# Brushless_2015RevA1_OptEnc.net
KiCad netlist of a schematic drawn in EAGLE
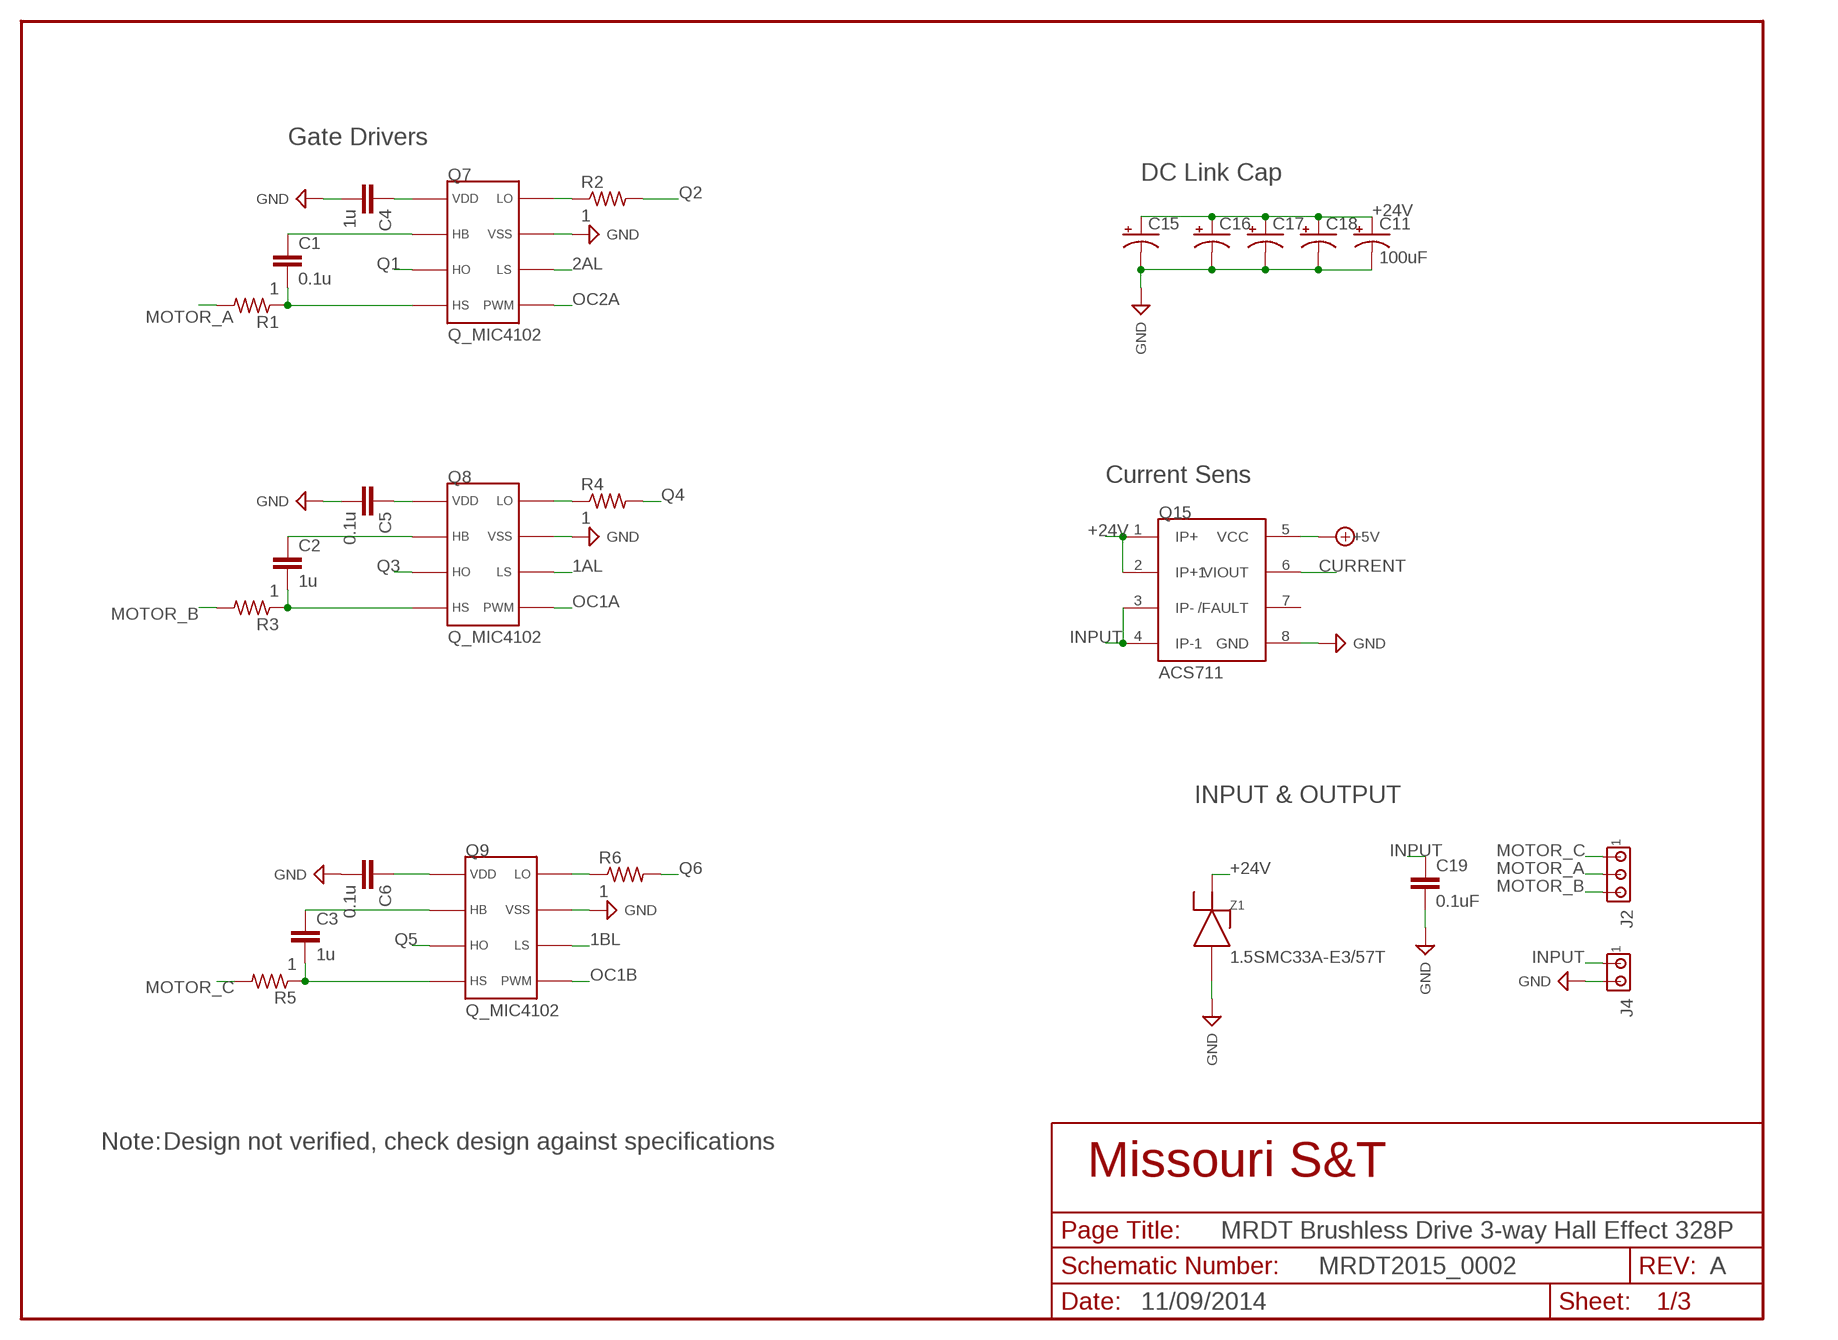
[diagram p0: schematic, sheet 1]
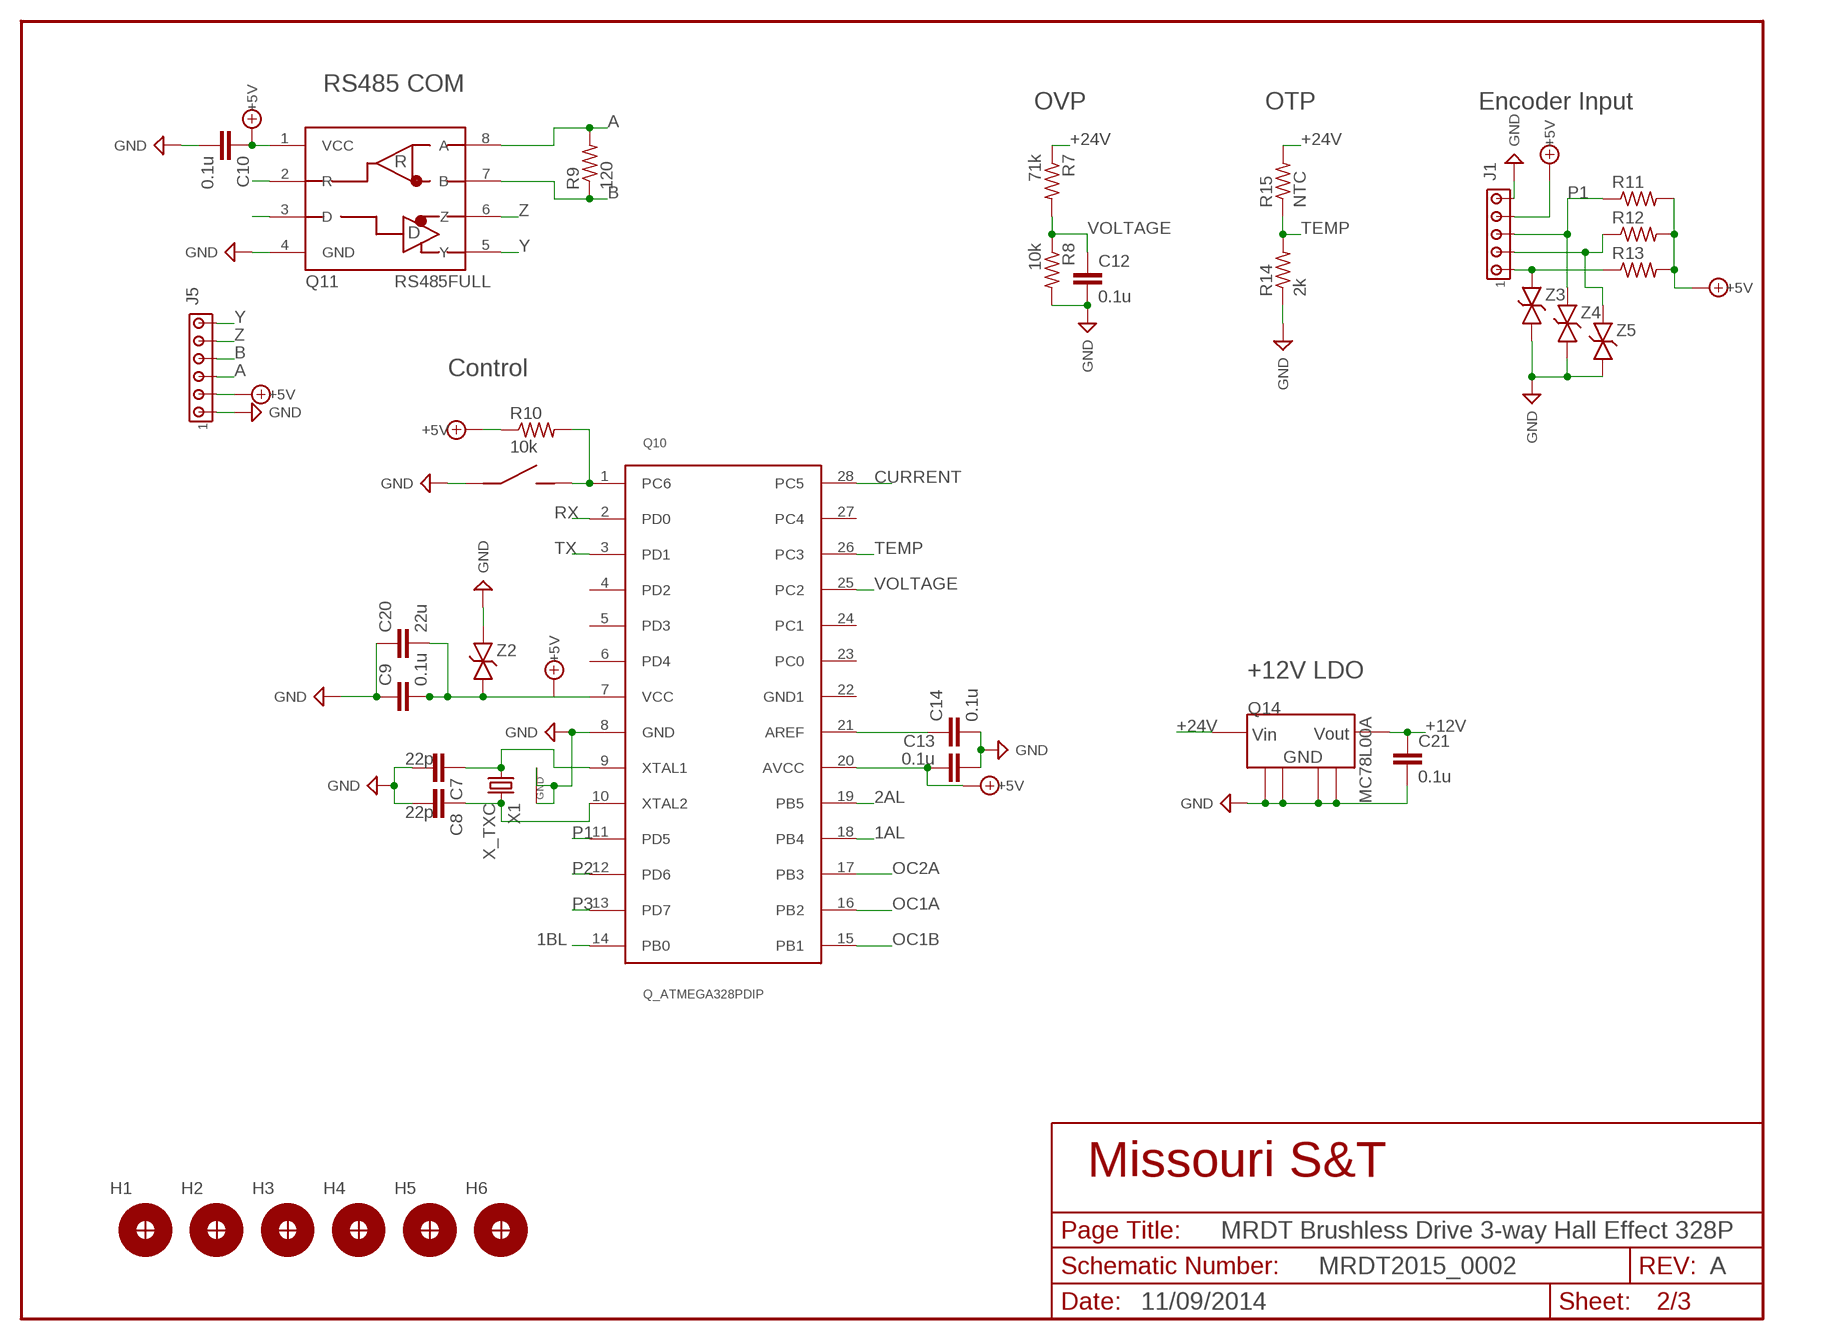
[diagram p1: schematic, sheet 2]
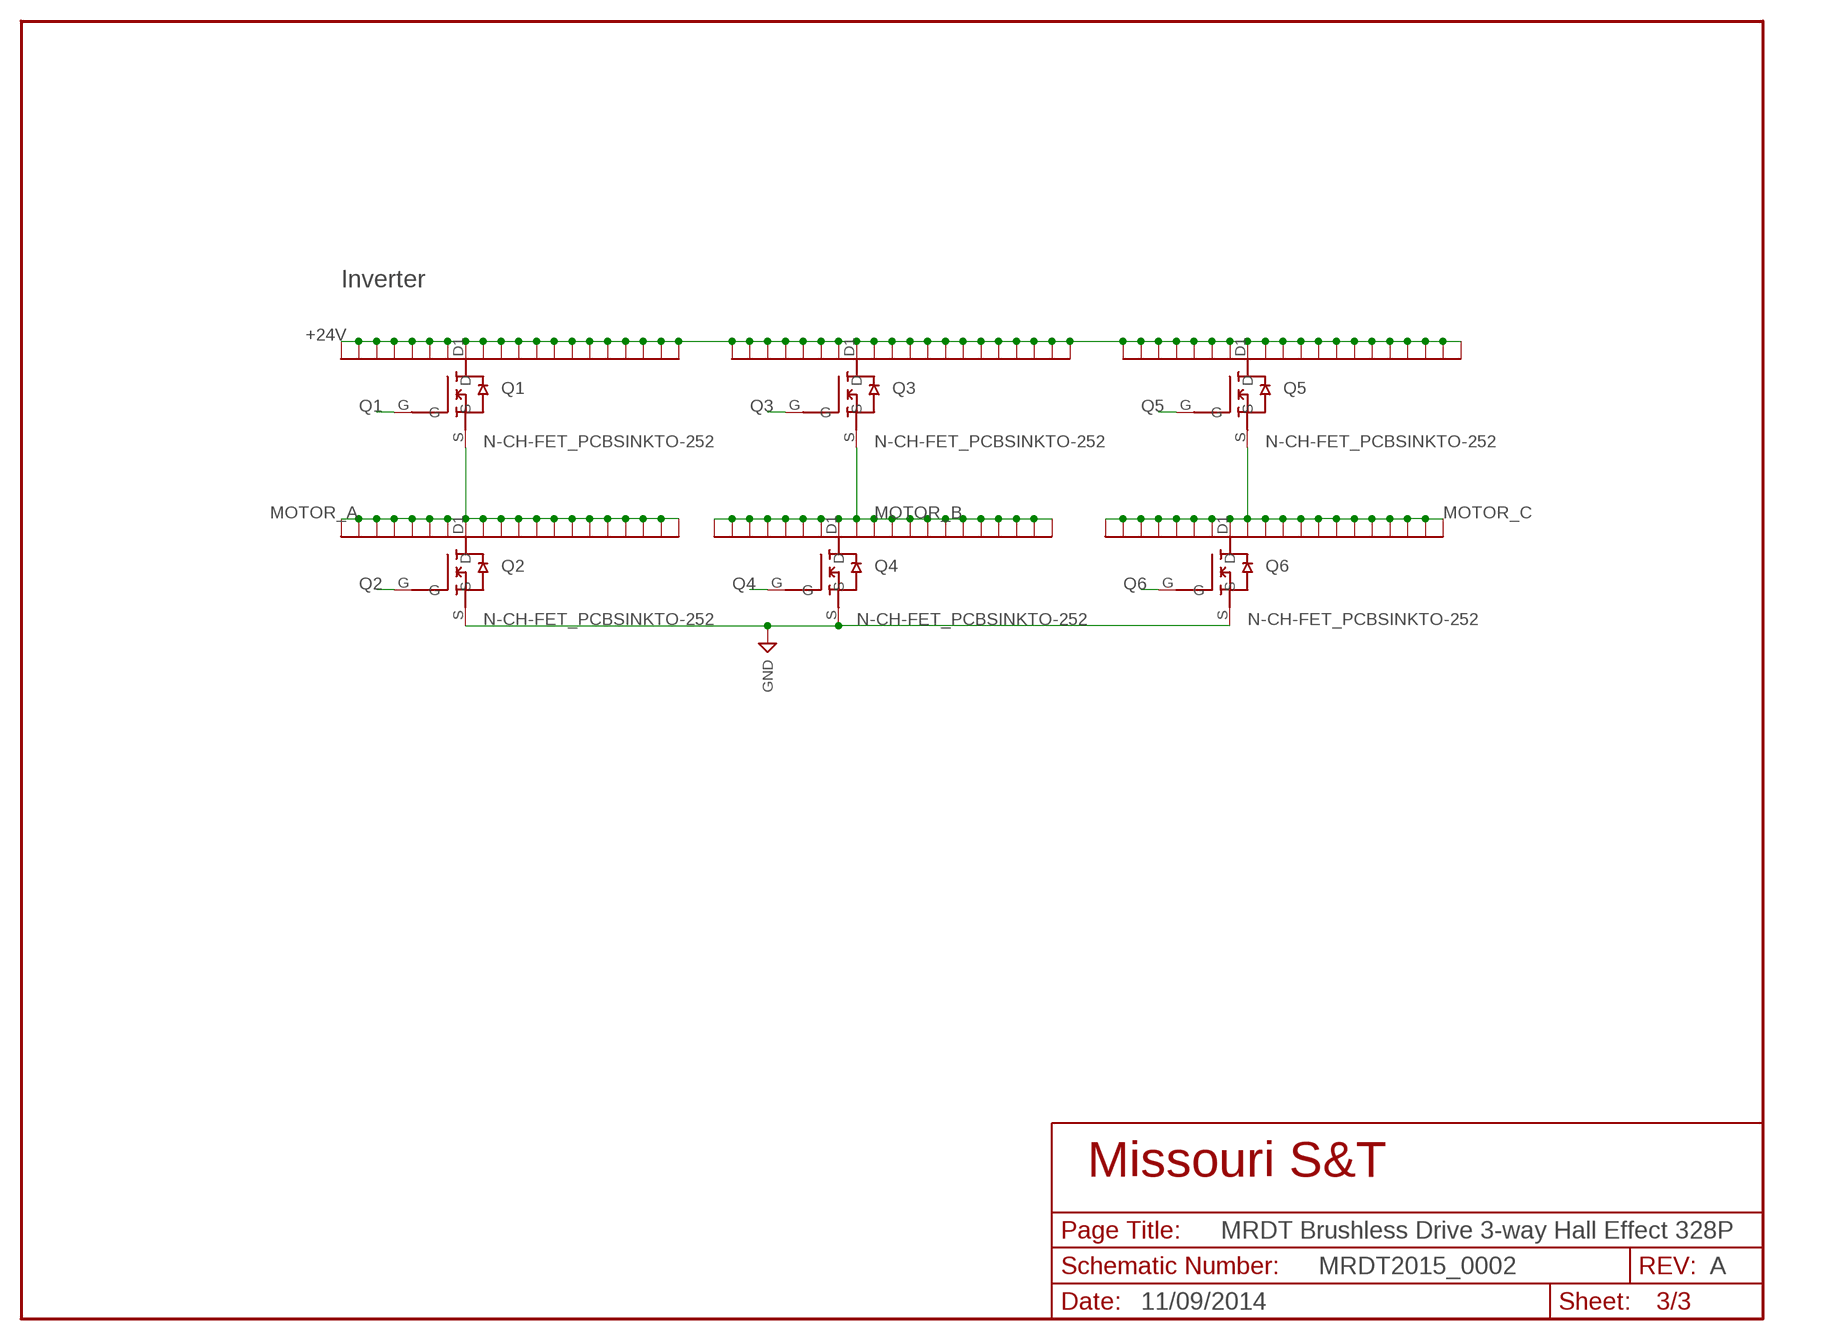
[diagram p2: schematic, sheet 3]

(export (version "E")
  (design (tool "Eeschema 10.0.6"))
  (components
    (comp (ref "C7")
      (value "22p")
      (footprint "eagle-import:C_1206")
      (libsource (lib "eagle-import") (part "Master_C_CAP_1206"))
    )
    (comp (ref "C8")
      (value "22p")
      (footprint "eagle-import:C_1206")
      (libsource (lib "eagle-import") (part "Master_C_CAP_1206"))
    )
    (comp (ref "C9")
      (value "0.1u")
      (footprint "eagle-import:C_0805")
      (libsource (lib "eagle-import") (part "Master_C_CAP_0805"))
    )
    (comp (ref "C10")
      (value "0.1u")
      (footprint "eagle-import:C_0805")
      (libsource (lib "eagle-import") (part "Master_C_CAP_0805"))
    )
    (comp (ref "C12")
      (value "0.1u")
      (footprint "eagle-import:C_0805")
      (libsource (lib "eagle-import") (part "Master_C_CAP_0805"))
    )
    (comp (ref "C13")
      (value "0.1u")
      (footprint "eagle-import:C_0805")
      (libsource (lib "eagle-import") (part "Master_C_CAP_0805"))
    )
    (comp (ref "C14")
      (value "0.1u")
      (footprint "eagle-import:C_0805")
      (libsource (lib "eagle-import") (part "Master_C_CAP_0805"))
    )
    (comp (ref "C20")
      (value "22u")
      (footprint "eagle-import:C_1206")
      (libsource (lib "eagle-import") (part "C_CAP_1206"))
    )
    (comp (ref "C21")
      (value "0.1u")
      (footprint "eagle-import:C_0805")
      (libsource (lib "eagle-import") (part "Master_C_CAP_0805"))
    )
    (comp (ref "H1")
      (value "H_MNTHOLE_#4")
      (footprint "eagle-import:H_MNTHOLE_#4")
      (libsource (lib "eagle-import") (part "H_MNTHOLE_#4"))
    )
    (comp (ref "H2")
      (value "H_MNTHOLE_#4")
      (footprint "eagle-import:H_MNTHOLE_#4")
      (libsource (lib "eagle-import") (part "H_MNTHOLE_#4"))
    )
    (comp (ref "H3")
      (value "H_MNTHOLE_#4")
      (footprint "eagle-import:H_MNTHOLE_#4")
      (libsource (lib "eagle-import") (part "H_MNTHOLE_#4"))
    )
    (comp (ref "H4")
      (value "H_MNTHOLE_#4")
      (footprint "eagle-import:H_MNTHOLE_#4")
      (libsource (lib "eagle-import") (part "H_MNTHOLE_#4"))
    )
    (comp (ref "H5")
      (value "H_MNTHOLE_#4")
      (footprint "eagle-import:H_MNTHOLE_#4")
      (libsource (lib "eagle-import") (part "H_MNTHOLE_#4"))
    )
    (comp (ref "H6")
      (value "H_MNTHOLE_#4")
      (footprint "eagle-import:H_MNTHOLE_#4")
      (libsource (lib "eagle-import") (part "H_MNTHOLE_#4"))
    )
    (comp (ref "J1")
      (value "J_MTA5P_100")
      (footprint "eagle-import:J_MTA100_5P")
      (libsource (lib "eagle-import") (part "J_MTA5P_100"))
    )
    (comp (ref "J3")
      (value "J_MC32857")
      (footprint "eagle-import:J_TOGGLE")
      (libsource (lib "eagle-import") (part "J_MC32857"))
    )
    (comp (ref "J5")
      (value "J_HDR1X6_MTA_100MIL")
      (footprint "eagle-import:J_MTA1X6_100MIL")
      (libsource (lib "eagle-import") (part "J_HDR1X6_MTA_100MIL"))
    )
    (comp (ref "Q10")
      (value "Q_ATMEGA328PDIP")
      (footprint "eagle-import:DIP28")
      (libsource (lib "eagle-import") (part "Q_ATMEGA328PDIP"))
    )
    (comp (ref "Q11")
      (value "RS485FULL")
      (footprint "eagle-import:SOIC8")
      (libsource (lib "eagle-import") (part "RS485FULL"))
    )
    (comp (ref "Q14")
      (value "MC78L00A")
      (footprint "eagle-import:SOIC8")
      (libsource (lib "eagle-import") (part "Q_LDOSOIC"))
    )
    (comp (ref "R7")
      (value "71k")
      (footprint "eagle-import:R_0805")
      (libsource (lib "eagle-import") (part "Master_R_RES_0805"))
    )
    (comp (ref "R8")
      (value "10k")
      (footprint "eagle-import:R_0805")
      (libsource (lib "eagle-import") (part "Master_R_RES_0805"))
    )
    (comp (ref "R9")
      (value "120")
      (footprint "eagle-import:R_0805")
      (libsource (lib "eagle-import") (part "Master_R_RES_0805"))
    )
    (comp (ref "R10")
      (value "10k")
      (footprint "eagle-import:R_0805")
      (libsource (lib "eagle-import") (part "R_RES_0805"))
    )
    (comp (ref "R11")
      (value "R_RES_1206")
      (footprint "eagle-import:R_1206")
      (libsource (lib "eagle-import") (part "R_RES_1206"))
    )
    (comp (ref "R12")
      (value "R_RES_1206")
      (footprint "eagle-import:R_1206")
      (libsource (lib "eagle-import") (part "R_RES_1206"))
    )
    (comp (ref "R13")
      (value "R_RES_1206")
      (footprint "eagle-import:R_1206")
      (libsource (lib "eagle-import") (part "R_RES_1206"))
    )
    (comp (ref "R14")
      (value "2k")
      (footprint "eagle-import:R_0805")
      (libsource (lib "eagle-import") (part "R_RES_0805"))
    )
    (comp (ref "R15")
      (value "NTC")
      (footprint "eagle-import:R_0805")
      (libsource (lib "eagle-import") (part "R_RES_0805"))
    )
    (comp (ref "X1")
      (value "X_TXC")
      (footprint "eagle-import:SMD_CRYSTAL")
      (libsource (lib "eagle-import") (part "X_TXC"))
    )
    (comp (ref "Z2")
      (value "Z_ESD0603")
      (footprint "eagle-import:0603")
      (libsource (lib "eagle-import") (part "Z_ESD0603"))
    )
    (comp (ref "Z3")
      (value "Z_ESD0603")
      (footprint "eagle-import:0603")
      (libsource (lib "eagle-import") (part "Z_ESD0603"))
    )
    (comp (ref "Z4")
      (value "Z_ESD0603")
      (footprint "eagle-import:0603")
      (libsource (lib "eagle-import") (part "Z_ESD0603"))
    )
    (comp (ref "Z5")
      (value "Z_ESD0603")
      (footprint "eagle-import:0603")
      (libsource (lib "eagle-import") (part "Z_ESD0603"))
    )
    (comp (ref "Q1")
      (value "N-CH-FET_PCBSINKTO-252")
      (footprint "eagle-import:TO-252-SINK")
      (libsource (lib "eagle-import") (part "N-CH-FET_PCBSINKTO-252"))
    )
    (comp (ref "Q2")
      (value "N-CH-FET_PCBSINKTO-252")
      (footprint "eagle-import:TO-252-SINK")
      (libsource (lib "eagle-import") (part "N-CH-FET_PCBSINKTO-252"))
    )
    (comp (ref "Q3")
      (value "N-CH-FET_PCBSINKTO-252")
      (footprint "eagle-import:TO-252-SINK")
      (libsource (lib "eagle-import") (part "N-CH-FET_PCBSINKTO-252"))
    )
    (comp (ref "Q4")
      (value "N-CH-FET_PCBSINKTO-252")
      (footprint "eagle-import:TO-252-SINK")
      (libsource (lib "eagle-import") (part "N-CH-FET_PCBSINKTO-252"))
    )
    (comp (ref "Q5")
      (value "N-CH-FET_PCBSINKTO-252")
      (footprint "eagle-import:TO-252-SINK")
      (libsource (lib "eagle-import") (part "N-CH-FET_PCBSINKTO-252"))
    )
    (comp (ref "Q6")
      (value "N-CH-FET_PCBSINKTO-252")
      (footprint "eagle-import:TO-252-SINK")
      (libsource (lib "eagle-import") (part "N-CH-FET_PCBSINKTO-252"))
    )
    (comp (ref "C1")
      (value "0.1u")
      (footprint "eagle-import:C_1206")
      (libsource (lib "eagle-import") (part "Master_C_CAP_1206"))
    )
    (comp (ref "C2")
      (value "1u")
      (footprint "eagle-import:C_1206")
      (libsource (lib "eagle-import") (part "Master_C_CAP_1206"))
    )
    (comp (ref "C3")
      (value "1u")
      (footprint "eagle-import:C_1206")
      (libsource (lib "eagle-import") (part "Master_C_CAP_1206"))
    )
    (comp (ref "C4")
      (value "1u")
      (footprint "eagle-import:C_1206")
      (libsource (lib "eagle-import") (part "Master_C_CAP_1206"))
    )
    (comp (ref "C5")
      (value "0.1u")
      (footprint "eagle-import:C_1206")
      (libsource (lib "eagle-import") (part "Master_C_CAP_1206"))
    )
    (comp (ref "C6")
      (value "0.1u")
      (footprint "eagle-import:C_1206")
      (libsource (lib "eagle-import") (part "Master_C_CAP_1206"))
    )
    (comp (ref "C11")
      (value "100uF")
      (footprint "eagle-import:C_8MM")
      (libsource (lib "eagle-import") (part "CAP_POL8MM"))
    )
    (comp (ref "C15")
      (value "CAP_POL8MM")
      (footprint "eagle-import:C_8MM")
      (libsource (lib "eagle-import") (part "CAP_POL8MM"))
    )
    (comp (ref "C16")
      (value "CAP_POL8MM")
      (footprint "eagle-import:C_8MM")
      (libsource (lib "eagle-import") (part "CAP_POL8MM"))
    )
    (comp (ref "C17")
      (value "CAP_POL8MM")
      (footprint "eagle-import:C_8MM")
      (libsource (lib "eagle-import") (part "CAP_POL8MM"))
    )
    (comp (ref "C18")
      (value "CAP_POL8MM")
      (footprint "eagle-import:C_8MM")
      (libsource (lib "eagle-import") (part "CAP_POL8MM"))
    )
    (comp (ref "C19")
      (value "0.1uF")
      (footprint "eagle-import:C_1206")
      (libsource (lib "eagle-import") (part "C_CAP_1206"))
    )
    (comp (ref "J2")
      (value "J_MTA3P_156")
      (footprint "eagle-import:J_MTA156_3P")
      (libsource (lib "eagle-import") (part "J_MTA3P_156"))
    )
    (comp (ref "J4")
      (value "J_HDR1X2_MTA_156MIL")
      (footprint "eagle-import:J_MTA1X2_156MIL")
      (libsource (lib "eagle-import") (part "J_HDR1X2_MTA_156MIL"))
    )
    (comp (ref "Q7")
      (value "Q_MIC4102")
      (footprint "eagle-import:SOIC8")
      (libsource (lib "eagle-import") (part "Q_MIC4102"))
    )
    (comp (ref "Q8")
      (value "Q_MIC4102")
      (footprint "eagle-import:SOIC8")
      (libsource (lib "eagle-import") (part "Q_MIC4102"))
    )
    (comp (ref "Q9")
      (value "Q_MIC4102")
      (footprint "eagle-import:SOIC8")
      (libsource (lib "eagle-import") (part "Q_MIC4102"))
    )
    (comp (ref "Q15")
      (value "ACS711")
      (footprint "eagle-import:SOIC8")
      (libsource (lib "eagle-import") (part "ACS711SOIC"))
    )
    (comp (ref "R1")
      (value "1")
      (footprint "eagle-import:R_0805")
      (libsource (lib "eagle-import") (part "Master_R_RES_0805"))
    )
    (comp (ref "R2")
      (value "1")
      (footprint "eagle-import:R_0805")
      (libsource (lib "eagle-import") (part "Master_R_RES_0805"))
    )
    (comp (ref "R3")
      (value "1")
      (footprint "eagle-import:R_0805")
      (libsource (lib "eagle-import") (part "Master_R_RES_0805"))
    )
    (comp (ref "R4")
      (value "1")
      (footprint "eagle-import:R_0805")
      (libsource (lib "eagle-import") (part "Master_R_RES_0805"))
    )
    (comp (ref "R5")
      (value "1")
      (footprint "eagle-import:R_0805")
      (libsource (lib "eagle-import") (part "Master_R_RES_0805"))
    )
    (comp (ref "R6")
      (value "1")
      (footprint "eagle-import:R_0805")
      (libsource (lib "eagle-import") (part "Master_R_RES_0805"))
    )
    (comp (ref "Z1")
      (value "Z_TVSDO214")
      (footprint "eagle-import:DO-214AC")
      (libsource (lib "eagle-import") (part "Z_TVSDO214"))
    )
  )
  (nets
    (net (code "1") (name "+5V") (class "Default")
      (node (ref "C10") (pin "1") (pinfunction "1_1") (pintype "passive"))
      (node (ref "C13") (pin "1") (pinfunction "1_1") (pintype "passive"))
      (node (ref "C20") (pin "2") (pinfunction "2_2") (pintype "passive"))
      (node (ref "C9") (pin "2") (pinfunction "2_2") (pintype "passive"))
      (node (ref "J1") (pin "4") (pinfunction "4_4") (pintype "passive"))
      (node (ref "J5") (pin "2") (pinfunction "2_2") (pintype "passive"))
      (node (ref "Q10") (pin "20") (pinfunction "AVCC_20") (pintype "bidirectional"))
      (node (ref "Q10") (pin "7") (pinfunction "VCC_7") (pintype "bidirectional"))
      (node (ref "Q11") (pin "1") (pinfunction "VCC_1") (pintype "bidirectional"))
      (node (ref "Q15") (pin "5") (pinfunction "VCC_5") (pintype "bidirectional"))
      (node (ref "R10") (pin "1") (pinfunction "1_1") (pintype "passive"))
      (node (ref "R11") (pin "2") (pinfunction "2_2") (pintype "passive"))
      (node (ref "R12") (pin "2") (pinfunction "2_2") (pintype "passive"))
      (node (ref "R13") (pin "2") (pinfunction "2_2") (pintype "passive"))
      (node (ref "Z2") (pin "1") (pinfunction "P$1_1") (pintype "bidirectional"))
    )
    (net (code "2") (name "+12V") (class "Default")
      (node (ref "C21") (pin "1") (pinfunction "1_1") (pintype "passive"))
      (node (ref "C4") (pin "1") (pinfunction "1_1") (pintype "passive"))
      (node (ref "C5") (pin "1") (pinfunction "1_1") (pintype "passive"))
      (node (ref "C6") (pin "1") (pinfunction "1_1") (pintype "passive"))
      (node (ref "Q14") (pin "1") (pinfunction "VOUT_1") (pintype "bidirectional"))
      (node (ref "Q7") (pin "1") (pinfunction "VDD_1") (pintype "bidirectional"))
      (node (ref "Q8") (pin "1") (pinfunction "VDD_1") (pintype "bidirectional"))
      (node (ref "Q9") (pin "1") (pinfunction "VDD_1") (pintype "bidirectional"))
    )
    (net (code "3") (name "+24V") (class "Default")
      (node (ref "C11") (pin "+") (pinfunction "+_+") (pintype "passive"))
      (node (ref "C15") (pin "+") (pinfunction "+_+") (pintype "passive"))
      (node (ref "C16") (pin "+") (pinfunction "+_+") (pintype "passive"))
      (node (ref "C17") (pin "+") (pinfunction "+_+") (pintype "passive"))
      (node (ref "C18") (pin "+") (pinfunction "+_+") (pintype "passive"))
      (node (ref "Q1") (pin "D1") (pinfunction "D_D1") (pintype "bidirectional"))
      (node (ref "Q1") (pin "D10") (pinfunction "P$9_D10") (pintype "bidirectional"))
      (node (ref "Q1") (pin "D11") (pinfunction "P$10_D11") (pintype "bidirectional"))
      (node (ref "Q1") (pin "D12") (pinfunction "P$11_D12") (pintype "bidirectional"))
      (node (ref "Q1") (pin "D13") (pinfunction "P$12_D13") (pintype "bidirectional"))
      (node (ref "Q1") (pin "D14") (pinfunction "P$13_D14") (pintype "bidirectional"))
      (node (ref "Q1") (pin "D15") (pinfunction "P$14_D15") (pintype "bidirectional"))
      (node (ref "Q1") (pin "D16") (pinfunction "P$15_D16") (pintype "bidirectional"))
      (node (ref "Q1") (pin "D17") (pinfunction "P$16_D17") (pintype "bidirectional"))
      (node (ref "Q1") (pin "D18") (pinfunction "P$17_D18") (pintype "bidirectional"))
      (node (ref "Q1") (pin "D19") (pinfunction "P$18_D19") (pintype "bidirectional"))
      (node (ref "Q1") (pin "D2") (pinfunction "P$1_D2") (pintype "bidirectional"))
      (node (ref "Q1") (pin "D20") (pinfunction "P$19_D20") (pintype "bidirectional"))
      (node (ref "Q1") (pin "D3") (pinfunction "P$2_D3") (pintype "bidirectional"))
      (node (ref "Q1") (pin "D4") (pinfunction "P$3_D4") (pintype "bidirectional"))
      (node (ref "Q1") (pin "D5") (pinfunction "P$4_D5") (pintype "bidirectional"))
      (node (ref "Q1") (pin "D6") (pinfunction "P$5_D6") (pintype "bidirectional"))
      (node (ref "Q1") (pin "D7") (pinfunction "P$6_D7") (pintype "bidirectional"))
      (node (ref "Q1") (pin "D8") (pinfunction "P$7_D8") (pintype "bidirectional"))
      (node (ref "Q1") (pin "D9") (pinfunction "P$8_D9") (pintype "bidirectional"))
      (node (ref "Q14") (pin "8") (pinfunction "VIN_8") (pintype "bidirectional"))
      (node (ref "Q15") (pin "1") (pinfunction "IP+_1") (pintype "bidirectional"))
      (node (ref "Q15") (pin "2") (pinfunction "IP+1_2") (pintype "bidirectional"))
      (node (ref "Q3") (pin "D1") (pinfunction "D_D1") (pintype "bidirectional"))
      (node (ref "Q3") (pin "D10") (pinfunction "P$9_D10") (pintype "bidirectional"))
      (node (ref "Q3") (pin "D11") (pinfunction "P$10_D11") (pintype "bidirectional"))
      (node (ref "Q3") (pin "D12") (pinfunction "P$11_D12") (pintype "bidirectional"))
      (node (ref "Q3") (pin "D13") (pinfunction "P$12_D13") (pintype "bidirectional"))
      (node (ref "Q3") (pin "D14") (pinfunction "P$13_D14") (pintype "bidirectional"))
      (node (ref "Q3") (pin "D15") (pinfunction "P$14_D15") (pintype "bidirectional"))
      (node (ref "Q3") (pin "D16") (pinfunction "P$15_D16") (pintype "bidirectional"))
      (node (ref "Q3") (pin "D17") (pinfunction "P$16_D17") (pintype "bidirectional"))
      (node (ref "Q3") (pin "D18") (pinfunction "P$17_D18") (pintype "bidirectional"))
      (node (ref "Q3") (pin "D19") (pinfunction "P$18_D19") (pintype "bidirectional"))
      (node (ref "Q3") (pin "D2") (pinfunction "P$1_D2") (pintype "bidirectional"))
      (node (ref "Q3") (pin "D20") (pinfunction "P$19_D20") (pintype "bidirectional"))
      (node (ref "Q3") (pin "D3") (pinfunction "P$2_D3") (pintype "bidirectional"))
      (node (ref "Q3") (pin "D4") (pinfunction "P$3_D4") (pintype "bidirectional"))
      (node (ref "Q3") (pin "D5") (pinfunction "P$4_D5") (pintype "bidirectional"))
      (node (ref "Q3") (pin "D6") (pinfunction "P$5_D6") (pintype "bidirectional"))
      (node (ref "Q3") (pin "D7") (pinfunction "P$6_D7") (pintype "bidirectional"))
      (node (ref "Q3") (pin "D8") (pinfunction "P$7_D8") (pintype "bidirectional"))
      (node (ref "Q3") (pin "D9") (pinfunction "P$8_D9") (pintype "bidirectional"))
      (node (ref "Q5") (pin "D1") (pinfunction "D_D1") (pintype "bidirectional"))
      (node (ref "Q5") (pin "D10") (pinfunction "P$9_D10") (pintype "bidirectional"))
      (node (ref "Q5") (pin "D11") (pinfunction "P$10_D11") (pintype "bidirectional"))
      (node (ref "Q5") (pin "D12") (pinfunction "P$11_D12") (pintype "bidirectional"))
      (node (ref "Q5") (pin "D13") (pinfunction "P$12_D13") (pintype "bidirectional"))
      (node (ref "Q5") (pin "D14") (pinfunction "P$13_D14") (pintype "bidirectional"))
      (node (ref "Q5") (pin "D15") (pinfunction "P$14_D15") (pintype "bidirectional"))
      (node (ref "Q5") (pin "D16") (pinfunction "P$15_D16") (pintype "bidirectional"))
      (node (ref "Q5") (pin "D17") (pinfunction "P$16_D17") (pintype "bidirectional"))
      (node (ref "Q5") (pin "D18") (pinfunction "P$17_D18") (pintype "bidirectional"))
      (node (ref "Q5") (pin "D19") (pinfunction "P$18_D19") (pintype "bidirectional"))
      (node (ref "Q5") (pin "D2") (pinfunction "P$1_D2") (pintype "bidirectional"))
      (node (ref "Q5") (pin "D20") (pinfunction "P$19_D20") (pintype "bidirectional"))
      (node (ref "Q5") (pin "D3") (pinfunction "P$2_D3") (pintype "bidirectional"))
      (node (ref "Q5") (pin "D4") (pinfunction "P$3_D4") (pintype "bidirectional"))
      (node (ref "Q5") (pin "D5") (pinfunction "P$4_D5") (pintype "bidirectional"))
      (node (ref "Q5") (pin "D6") (pinfunction "P$5_D6") (pintype "bidirectional"))
      (node (ref "Q5") (pin "D7") (pinfunction "P$6_D7") (pintype "bidirectional"))
      (node (ref "Q5") (pin "D8") (pinfunction "P$7_D8") (pintype "bidirectional"))
      (node (ref "Q5") (pin "D9") (pinfunction "P$8_D9") (pintype "bidirectional"))
      (node (ref "R15") (pin "2") (pinfunction "2_2") (pintype "passive"))
      (node (ref "R7") (pin "1") (pinfunction "1_1") (pintype "passive"))
      (node (ref "Z1") (pin "C") (pinfunction "C_C") (pintype "bidirectional"))
    )
    (net (code "4") (name "1AL") (class "Default")
      (node (ref "Q10") (pin "18") (pinfunction "PB4_18") (pintype "bidirectional"))
      (node (ref "Q8") (pin "6") (pinfunction "LS_6") (pintype "bidirectional"))
    )
    (net (code "5") (name "1BL") (class "Default")
      (node (ref "Q10") (pin "14") (pinfunction "PB0_14") (pintype "bidirectional"))
      (node (ref "Q9") (pin "6") (pinfunction "LS_6") (pintype "bidirectional"))
    )
    (net (code "6") (name "2AL") (class "Default")
      (node (ref "Q10") (pin "19") (pinfunction "PB5_19") (pintype "bidirectional"))
      (node (ref "Q7") (pin "6") (pinfunction "LS_6") (pintype "bidirectional"))
    )
    (net (code "7") (name "A") (class "Default")
      (node (ref "J5") (pin "3") (pinfunction "3_3") (pintype "passive"))
      (node (ref "Q11") (pin "8") (pinfunction "A_8") (pintype "bidirectional"))
      (node (ref "R9") (pin "2") (pinfunction "2_2") (pintype "passive"))
    )
    (net (code "8") (name "B") (class "Default")
      (node (ref "J5") (pin "4") (pinfunction "4_4") (pintype "passive"))
      (node (ref "Q11") (pin "7") (pinfunction "B_7") (pintype "bidirectional"))
      (node (ref "R9") (pin "1") (pinfunction "1_1") (pintype "passive"))
    )
    (net (code "9") (name "CURRENT") (class "Default")
      (node (ref "Q10") (pin "28") (pinfunction "PC5_28") (pintype "bidirectional"))
      (node (ref "Q15") (pin "6") (pinfunction "VIOUT_6") (pintype "bidirectional"))
    )
    (net (code "10") (name "GND") (class "Default")
      (node (ref "C10") (pin "2") (pinfunction "2_2") (pintype "passive"))
      (node (ref "C11") (pin "-") (pinfunction "-_-") (pintype "passive"))
      (node (ref "C12") (pin "2") (pinfunction "2_2") (pintype "passive"))
      (node (ref "C13") (pin "2") (pinfunction "2_2") (pintype "passive"))
      (node (ref "C14") (pin "2") (pinfunction "2_2") (pintype "passive"))
      (node (ref "C15") (pin "-") (pinfunction "-_-") (pintype "passive"))
      (node (ref "C16") (pin "-") (pinfunction "-_-") (pintype "passive"))
      (node (ref "C17") (pin "-") (pinfunction "-_-") (pintype "passive"))
      (node (ref "C18") (pin "-") (pinfunction "-_-") (pintype "passive"))
      (node (ref "C19") (pin "2") (pinfunction "2_2") (pintype "passive"))
      (node (ref "C20") (pin "1") (pinfunction "1_1") (pintype "passive"))
      (node (ref "C21") (pin "2") (pinfunction "2_2") (pintype "passive"))
      (node (ref "C4") (pin "2") (pinfunction "2_2") (pintype "passive"))
      (node (ref "C5") (pin "2") (pinfunction "2_2") (pintype "passive"))
      (node (ref "C6") (pin "2") (pinfunction "2_2") (pintype "passive"))
      (node (ref "C7") (pin "2") (pinfunction "2_2") (pintype "passive"))
      (node (ref "C8") (pin "2") (pinfunction "2_2") (pintype "passive"))
      (node (ref "C9") (pin "1") (pinfunction "1_1") (pintype "passive"))
      (node (ref "J1") (pin "5") (pinfunction "5_5") (pintype "passive"))
      (node (ref "J3") (pin "P$1") (pinfunction "1_P$1") (pintype "bidirectional"))
      (node (ref "J4") (pin "2") (pinfunction "2_2") (pintype "passive"))
      (node (ref "J5") (pin "1") (pinfunction "1_1") (pintype "passive"))
      (node (ref "Q10") (pin "8") (pinfunction "GND_8") (pintype "bidirectional"))
      (node (ref "Q11") (pin "4") (pinfunction "GND_4") (pintype "bidirectional"))
      (node (ref "Q14") (pin "2") (pinfunction "GND_2") (pintype "bidirectional"))
      (node (ref "Q14") (pin "3") (pinfunction "GND1_3") (pintype "bidirectional"))
      (node (ref "Q14") (pin "6") (pinfunction "GND3_6") (pintype "bidirectional"))
      (node (ref "Q14") (pin "7") (pinfunction "GND2_7") (pintype "bidirectional"))
      (node (ref "Q15") (pin "8") (pinfunction "GND_8") (pintype "bidirectional"))
      (node (ref "Q2") (pin "S") (pinfunction "S_S") (pintype "bidirectional"))
      (node (ref "Q4") (pin "S") (pinfunction "S_S") (pintype "bidirectional"))
      (node (ref "Q6") (pin "S") (pinfunction "S_S") (pintype "bidirectional"))
      (node (ref "Q7") (pin "7") (pinfunction "VSS_7") (pintype "bidirectional"))
      (node (ref "Q8") (pin "7") (pinfunction "VSS_7") (pintype "bidirectional"))
      (node (ref "Q9") (pin "7") (pinfunction "VSS_7") (pintype "bidirectional"))
      (node (ref "R14") (pin "1") (pinfunction "1_1") (pintype "passive"))
      (node (ref "R8") (pin "2") (pinfunction "2_2") (pintype "passive"))
      (node (ref "X1") (pin "2") (pinfunction "GND1_2") (pintype "bidirectional"))
      (node (ref "X1") (pin "4") (pinfunction "GND2_4") (pintype "bidirectional"))
      (node (ref "Z1") (pin "A") (pinfunction "A_A") (pintype "bidirectional"))
      (node (ref "Z2") (pin "2") (pinfunction "P$2_2") (pintype "bidirectional"))
      (node (ref "Z3") (pin "1") (pinfunction "P$1_1") (pintype "bidirectional"))
      (node (ref "Z4") (pin "1") (pinfunction "P$1_1") (pintype "bidirectional"))
      (node (ref "Z5") (pin "1") (pinfunction "P$1_1") (pintype "bidirectional"))
    )
    (net (code "11") (name "INPUT") (class "Default")
      (node (ref "C19") (pin "1") (pinfunction "1_1") (pintype "passive"))
      (node (ref "J4") (pin "1") (pinfunction "1_1") (pintype "passive"))
      (node (ref "Q15") (pin "3") (pinfunction "IP-_3") (pintype "bidirectional"))
      (node (ref "Q15") (pin "4") (pinfunction "IP-1_4") (pintype "bidirectional"))
    )
    (net (code "12") (name "MOTOR_A") (class "Default")
      (node (ref "J2") (pin "2") (pinfunction "2_2") (pintype "passive"))
      (node (ref "Q1") (pin "S") (pinfunction "S_S") (pintype "bidirectional"))
      (node (ref "Q2") (pin "D1") (pinfunction "D_D1") (pintype "bidirectional"))
      (node (ref "Q2") (pin "D10") (pinfunction "P$9_D10") (pintype "bidirectional"))
      (node (ref "Q2") (pin "D11") (pinfunction "P$10_D11") (pintype "bidirectional"))
      (node (ref "Q2") (pin "D12") (pinfunction "P$11_D12") (pintype "bidirectional"))
      (node (ref "Q2") (pin "D13") (pinfunction "P$12_D13") (pintype "bidirectional"))
      (node (ref "Q2") (pin "D14") (pinfunction "P$13_D14") (pintype "bidirectional"))
      (node (ref "Q2") (pin "D15") (pinfunction "P$14_D15") (pintype "bidirectional"))
      (node (ref "Q2") (pin "D16") (pinfunction "P$15_D16") (pintype "bidirectional"))
      (node (ref "Q2") (pin "D17") (pinfunction "P$16_D17") (pintype "bidirectional"))
      (node (ref "Q2") (pin "D18") (pinfunction "P$17_D18") (pintype "bidirectional"))
      (node (ref "Q2") (pin "D19") (pinfunction "P$18_D19") (pintype "bidirectional"))
      (node (ref "Q2") (pin "D2") (pinfunction "P$1_D2") (pintype "bidirectional"))
      (node (ref "Q2") (pin "D20") (pinfunction "P$19_D20") (pintype "bidirectional"))
      (node (ref "Q2") (pin "D3") (pinfunction "P$2_D3") (pintype "bidirectional"))
      (node (ref "Q2") (pin "D4") (pinfunction "P$3_D4") (pintype "bidirectional"))
      (node (ref "Q2") (pin "D5") (pinfunction "P$4_D5") (pintype "bidirectional"))
      (node (ref "Q2") (pin "D6") (pinfunction "P$5_D6") (pintype "bidirectional"))
      (node (ref "Q2") (pin "D7") (pinfunction "P$6_D7") (pintype "bidirectional"))
      (node (ref "Q2") (pin "D8") (pinfunction "P$7_D8") (pintype "bidirectional"))
      (node (ref "Q2") (pin "D9") (pinfunction "P$8_D9") (pintype "bidirectional"))
      (node (ref "R1") (pin "2") (pinfunction "2_2") (pintype "passive"))
    )
    (net (code "13") (name "MOTOR_B") (class "Default")
      (node (ref "J2") (pin "3") (pinfunction "3_3") (pintype "passive"))
      (node (ref "Q3") (pin "S") (pinfunction "S_S") (pintype "bidirectional"))
      (node (ref "Q4") (pin "D1") (pinfunction "D_D1") (pintype "bidirectional"))
      (node (ref "Q4") (pin "D10") (pinfunction "P$9_D10") (pintype "bidirectional"))
      (node (ref "Q4") (pin "D11") (pinfunction "P$10_D11") (pintype "bidirectional"))
      (node (ref "Q4") (pin "D12") (pinfunction "P$11_D12") (pintype "bidirectional"))
      (node (ref "Q4") (pin "D13") (pinfunction "P$12_D13") (pintype "bidirectional"))
      (node (ref "Q4") (pin "D14") (pinfunction "P$13_D14") (pintype "bidirectional"))
      (node (ref "Q4") (pin "D15") (pinfunction "P$14_D15") (pintype "bidirectional"))
      (node (ref "Q4") (pin "D16") (pinfunction "P$15_D16") (pintype "bidirectional"))
      (node (ref "Q4") (pin "D17") (pinfunction "P$16_D17") (pintype "bidirectional"))
      (node (ref "Q4") (pin "D18") (pinfunction "P$17_D18") (pintype "bidirectional"))
      (node (ref "Q4") (pin "D19") (pinfunction "P$18_D19") (pintype "bidirectional"))
      (node (ref "Q4") (pin "D2") (pinfunction "P$1_D2") (pintype "bidirectional"))
      (node (ref "Q4") (pin "D20") (pinfunction "P$19_D20") (pintype "bidirectional"))
      (node (ref "Q4") (pin "D3") (pinfunction "P$2_D3") (pintype "bidirectional"))
      (node (ref "Q4") (pin "D4") (pinfunction "P$3_D4") (pintype "bidirectional"))
      (node (ref "Q4") (pin "D5") (pinfunction "P$4_D5") (pintype "bidirectional"))
      (node (ref "Q4") (pin "D6") (pinfunction "P$5_D6") (pintype "bidirectional"))
      (node (ref "Q4") (pin "D7") (pinfunction "P$6_D7") (pintype "bidirectional"))
      (node (ref "Q4") (pin "D8") (pinfunction "P$7_D8") (pintype "bidirectional"))
      (node (ref "Q4") (pin "D9") (pinfunction "P$8_D9") (pintype "bidirectional"))
      (node (ref "R3") (pin "2") (pinfunction "2_2") (pintype "passive"))
    )
    (net (code "14") (name "MOTOR_C") (class "Default")
      (node (ref "J2") (pin "1") (pinfunction "1_1") (pintype "passive"))
      (node (ref "Q5") (pin "S") (pinfunction "S_S") (pintype "bidirectional"))
      (node (ref "Q6") (pin "D1") (pinfunction "D_D1") (pintype "bidirectional"))
      (node (ref "Q6") (pin "D10") (pinfunction "P$9_D10") (pintype "bidirectional"))
      (node (ref "Q6") (pin "D11") (pinfunction "P$10_D11") (pintype "bidirectional"))
      (node (ref "Q6") (pin "D12") (pinfunction "P$11_D12") (pintype "bidirectional"))
      (node (ref "Q6") (pin "D13") (pinfunction "P$12_D13") (pintype "bidirectional"))
      (node (ref "Q6") (pin "D14") (pinfunction "P$13_D14") (pintype "bidirectional"))
      (node (ref "Q6") (pin "D15") (pinfunction "P$14_D15") (pintype "bidirectional"))
      (node (ref "Q6") (pin "D16") (pinfunction "P$15_D16") (pintype "bidirectional"))
      (node (ref "Q6") (pin "D17") (pinfunction "P$16_D17") (pintype "bidirectional"))
      (node (ref "Q6") (pin "D18") (pinfunction "P$17_D18") (pintype "bidirectional"))
      (node (ref "Q6") (pin "D19") (pinfunction "P$18_D19") (pintype "bidirectional"))
      (node (ref "Q6") (pin "D2") (pinfunction "P$1_D2") (pintype "bidirectional"))
      (node (ref "Q6") (pin "D20") (pinfunction "P$19_D20") (pintype "bidirectional"))
      (node (ref "Q6") (pin "D3") (pinfunction "P$2_D3") (pintype "bidirectional"))
      (node (ref "Q6") (pin "D4") (pinfunction "P$3_D4") (pintype "bidirectional"))
      (node (ref "Q6") (pin "D5") (pinfunction "P$4_D5") (pintype "bidirectional"))
      (node (ref "Q6") (pin "D6") (pinfunction "P$5_D6") (pintype "bidirectional"))
      (node (ref "Q6") (pin "D7") (pinfunction "P$6_D7") (pintype "bidirectional"))
      (node (ref "Q6") (pin "D8") (pinfunction "P$7_D8") (pintype "bidirectional"))
      (node (ref "Q6") (pin "D9") (pinfunction "P$8_D9") (pintype "bidirectional"))
      (node (ref "R5") (pin "2") (pinfunction "2_2") (pintype "passive"))
    )
    (net (code "15") (name "Net-(J3-2)") (class "Default")
      (node (ref "J3") (pin "P$2") (pinfunction "2_P$2") (pintype "bidirectional"))
      (node (ref "Q10") (pin "1") (pinfunction "PC6_1") (pintype "bidirectional"))
      (node (ref "R10") (pin "2") (pinfunction "2_2") (pintype "passive"))
    )
    (net (code "16") (name "Net-(Q7-HB)") (class "Default")
      (node (ref "C1") (pin "1") (pinfunction "1_1") (pintype "passive"))
      (node (ref "Q7") (pin "2") (pinfunction "HB_2") (pintype "bidirectional"))
    )
    (net (code "17") (name "Net-(Q7-HS)") (class "Default")
      (node (ref "C1") (pin "2") (pinfunction "2_2") (pintype "passive"))
      (node (ref "Q7") (pin "4") (pinfunction "HS_4") (pintype "bidirectional"))
      (node (ref "R1") (pin "1") (pinfunction "1_1") (pintype "passive"))
    )
    (net (code "18") (name "Net-(Q7-LO)") (class "Default")
      (node (ref "Q7") (pin "8") (pinfunction "LO_8") (pintype "bidirectional"))
      (node (ref "R2") (pin "1") (pinfunction "1_1") (pintype "passive"))
    )
    (net (code "19") (name "Net-(Q8-HB)") (class "Default")
      (node (ref "C2") (pin "1") (pinfunction "1_1") (pintype "passive"))
      (node (ref "Q8") (pin "2") (pinfunction "HB_2") (pintype "bidirectional"))
    )
    (net (code "20") (name "Net-(Q8-HS)") (class "Default")
      (node (ref "C2") (pin "2") (pinfunction "2_2") (pintype "passive"))
      (node (ref "Q8") (pin "4") (pinfunction "HS_4") (pintype "bidirectional"))
      (node (ref "R3") (pin "1") (pinfunction "1_1") (pintype "passive"))
    )
    (net (code "21") (name "Net-(Q8-LO)") (class "Default")
      (node (ref "Q8") (pin "8") (pinfunction "LO_8") (pintype "bidirectional"))
      (node (ref "R4") (pin "1") (pinfunction "1_1") (pintype "passive"))
    )
    (net (code "22") (name "Net-(Q9-HB)") (class "Default")
      (node (ref "C3") (pin "1") (pinfunction "1_1") (pintype "passive"))
      (node (ref "Q9") (pin "2") (pinfunction "HB_2") (pintype "bidirectional"))
    )
    (net (code "23") (name "Net-(Q9-HS)") (class "Default")
      (node (ref "C3") (pin "2") (pinfunction "2_2") (pintype "passive"))
      (node (ref "Q9") (pin "4") (pinfunction "HS_4") (pintype "bidirectional"))
      (node (ref "R5") (pin "1") (pinfunction "1_1") (pintype "passive"))
    )
    (net (code "24") (name "Net-(Q9-LO)") (class "Default")
      (node (ref "Q9") (pin "8") (pinfunction "LO_8") (pintype "bidirectional"))
      (node (ref "R6") (pin "1") (pinfunction "1_1") (pintype "passive"))
    )
    (net (code "25") (name "Net-(Q10-AREF)") (class "Default")
      (node (ref "C14") (pin "1") (pinfunction "1_1") (pintype "passive"))
      (node (ref "Q10") (pin "21") (pinfunction "AREF_21") (pintype "bidirectional"))
    )
    (net (code "26") (name "Net-(Q10-XTAL1)") (class "Default")
      (node (ref "C7") (pin "1") (pinfunction "1_1") (pintype "passive"))
      (node (ref "Q10") (pin "9") (pinfunction "XTAL1_9") (pintype "bidirectional"))
      (node (ref "X1") (pin "1") (pinfunction "1_1") (pintype "passive"))
    )
    (net (code "27") (name "Net-(Q10-XTAL2)") (class "Default")
      (node (ref "C8") (pin "1") (pinfunction "1_1") (pintype "passive"))
      (node (ref "Q10") (pin "10") (pinfunction "XTAL2_10") (pintype "bidirectional"))
      (node (ref "X1") (pin "3") (pinfunction "2_3") (pintype "passive"))
    )
    (net (code "28") (name "OC1A") (class "Default")
      (node (ref "Q10") (pin "16") (pinfunction "PB2_16") (pintype "bidirectional"))
      (node (ref "Q8") (pin "5") (pinfunction "PWM_5") (pintype "bidirectional"))
    )
    (net (code "29") (name "OC1B") (class "Default")
      (node (ref "Q10") (pin "15") (pinfunction "PB1_15") (pintype "bidirectional"))
      (node (ref "Q9") (pin "5") (pinfunction "PWM_5") (pintype "bidirectional"))
    )
    (net (code "30") (name "OC2A") (class "Default")
      (node (ref "Q10") (pin "17") (pinfunction "PB3_17") (pintype "bidirectional"))
      (node (ref "Q7") (pin "5") (pinfunction "PWM_5") (pintype "bidirectional"))
    )
    (net (code "31") (name "P1") (class "Default")
      (node (ref "J1") (pin "3") (pinfunction "3_3") (pintype "passive"))
      (node (ref "Q10") (pin "11") (pinfunction "PD5_11") (pintype "bidirectional"))
      (node (ref "R11") (pin "1") (pinfunction "1_1") (pintype "passive"))
      (node (ref "Z4") (pin "2") (pinfunction "P$2_2") (pintype "bidirectional"))
    )
    (net (code "32") (name "P2") (class "Default")
      (node (ref "J1") (pin "2") (pinfunction "2_2") (pintype "passive"))
      (node (ref "Q10") (pin "12") (pinfunction "PD6_12") (pintype "bidirectional"))
      (node (ref "R12") (pin "1") (pinfunction "1_1") (pintype "passive"))
      (node (ref "Z5") (pin "2") (pinfunction "P$2_2") (pintype "bidirectional"))
    )
    (net (code "33") (name "P3") (class "Default")
      (node (ref "J1") (pin "1") (pinfunction "1_1") (pintype "passive"))
      (node (ref "Q10") (pin "13") (pinfunction "PD7_13") (pintype "bidirectional"))
      (node (ref "R13") (pin "1") (pinfunction "1_1") (pintype "passive"))
      (node (ref "Z3") (pin "2") (pinfunction "P$2_2") (pintype "bidirectional"))
    )
    (net (code "34") (name "Q1") (class "Default")
      (node (ref "Q1") (pin "G") (pinfunction "G_G") (pintype "bidirectional"))
      (node (ref "Q7") (pin "3") (pinfunction "HO_3") (pintype "bidirectional"))
    )
    (net (code "35") (name "Q2") (class "Default")
      (node (ref "Q2") (pin "G") (pinfunction "G_G") (pintype "bidirectional"))
      (node (ref "R2") (pin "2") (pinfunction "2_2") (pintype "passive"))
    )
    (net (code "36") (name "Q3") (class "Default")
      (node (ref "Q3") (pin "G") (pinfunction "G_G") (pintype "bidirectional"))
      (node (ref "Q8") (pin "3") (pinfunction "HO_3") (pintype "bidirectional"))
    )
    (net (code "37") (name "Q4") (class "Default")
      (node (ref "Q4") (pin "G") (pinfunction "G_G") (pintype "bidirectional"))
      (node (ref "R4") (pin "2") (pinfunction "2_2") (pintype "passive"))
    )
    (net (code "38") (name "Q5") (class "Default")
      (node (ref "Q5") (pin "G") (pinfunction "G_G") (pintype "bidirectional"))
      (node (ref "Q9") (pin "3") (pinfunction "HO_3") (pintype "bidirectional"))
    )
    (net (code "39") (name "Q6") (class "Default")
      (node (ref "Q6") (pin "G") (pinfunction "G_G") (pintype "bidirectional"))
      (node (ref "R6") (pin "2") (pinfunction "2_2") (pintype "passive"))
    )
    (net (code "40") (name "RX") (class "Default")
      (node (ref "Q10") (pin "2") (pinfunction "PD0_2") (pintype "bidirectional"))
      (node (ref "Q11") (pin "2") (pinfunction "R_2") (pintype "bidirectional"))
    )
    (net (code "41") (name "TEMP") (class "Default")
      (node (ref "Q10") (pin "26") (pinfunction "PC3_26") (pintype "bidirectional"))
      (node (ref "R14") (pin "2") (pinfunction "2_2") (pintype "passive"))
      (node (ref "R15") (pin "1") (pinfunction "1_1") (pintype "passive"))
    )
    (net (code "42") (name "TX") (class "Default")
      (node (ref "Q10") (pin "3") (pinfunction "PD1_3") (pintype "bidirectional"))
      (node (ref "Q11") (pin "3") (pinfunction "D_3") (pintype "bidirectional"))
    )
    (net (code "43") (name "VOLTAGE") (class "Default")
      (node (ref "C12") (pin "1") (pinfunction "1_1") (pintype "passive"))
      (node (ref "Q10") (pin "25") (pinfunction "PC2_25") (pintype "bidirectional"))
      (node (ref "R7") (pin "2") (pinfunction "2_2") (pintype "passive"))
      (node (ref "R8") (pin "1") (pinfunction "1_1") (pintype "passive"))
    )
    (net (code "44") (name "Y") (class "Default")
      (node (ref "J5") (pin "6") (pinfunction "6_6") (pintype "passive"))
      (node (ref "Q11") (pin "5") (pinfunction "Y_5") (pintype "bidirectional"))
    )
    (net (code "45") (name "Z") (class "Default")
      (node (ref "J5") (pin "5") (pinfunction "5_5") (pintype "passive"))
      (node (ref "Q11") (pin "6") (pinfunction "Z_6") (pintype "bidirectional"))
    )
    (net (code "46") (name "unconnected-(H1-Pad1)") (class "Default")
      (node (ref "H1") (pin "1") (pinfunction "1_1") (pintype "passive"))
    )
    (net (code "47") (name "unconnected-(H2-Pad1)") (class "Default")
      (node (ref "H2") (pin "1") (pinfunction "1_1") (pintype "passive"))
    )
    (net (code "48") (name "unconnected-(H3-Pad1)") (class "Default")
      (node (ref "H3") (pin "1") (pinfunction "1_1") (pintype "passive"))
    )
    (net (code "49") (name "unconnected-(H4-Pad1)") (class "Default")
      (node (ref "H4") (pin "1") (pinfunction "1_1") (pintype "passive"))
    )
    (net (code "50") (name "unconnected-(H5-Pad1)") (class "Default")
      (node (ref "H5") (pin "1") (pinfunction "1_1") (pintype "passive"))
    )
    (net (code "51") (name "unconnected-(H6-Pad1)") (class "Default")
      (node (ref "H6") (pin "1") (pinfunction "1_1") (pintype "passive"))
    )
    (net (code "52") (name "unconnected-(Q10-GND1-Pad22)") (class "Default")
      (node (ref "Q10") (pin "22") (pinfunction "GND1_22") (pintype "bidirectional"))
    )
    (net (code "53") (name "unconnected-(Q10-PC0-Pad23)") (class "Default")
      (node (ref "Q10") (pin "23") (pinfunction "PC0_23") (pintype "bidirectional"))
    )
    (net (code "54") (name "unconnected-(Q10-PC1-Pad24)") (class "Default")
      (node (ref "Q10") (pin "24") (pinfunction "PC1_24") (pintype "bidirectional"))
    )
    (net (code "55") (name "unconnected-(Q10-PC4-Pad27)") (class "Default")
      (node (ref "Q10") (pin "27") (pinfunction "PC4_27") (pintype "bidirectional"))
    )
    (net (code "56") (name "unconnected-(Q10-PD2-Pad4)") (class "Default")
      (node (ref "Q10") (pin "4") (pinfunction "PD2_4") (pintype "bidirectional"))
    )
    (net (code "57") (name "unconnected-(Q10-PD3-Pad5)") (class "Default")
      (node (ref "Q10") (pin "5") (pinfunction "PD3_5") (pintype "bidirectional"))
    )
    (net (code "58") (name "unconnected-(Q10-PD4-Pad6)") (class "Default")
      (node (ref "Q10") (pin "6") (pinfunction "PD4_6") (pintype "bidirectional"))
    )
    (net (code "59") (name "unconnected-(Q15-{slash}FAULT-Pad7)") (class "Default")
      (node (ref "Q15") (pin "7") (pinfunction "/FAULT_7") (pintype "bidirectional"))
    )
  )
)
